# Alimentations.net
KiCad netlist of a schematic drawn in Altium Designer
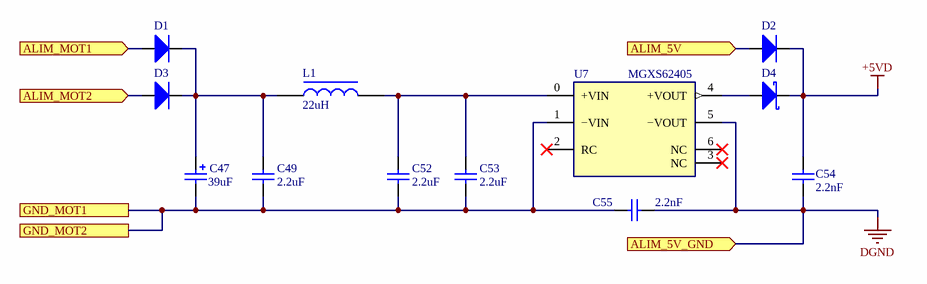
[diagram p0: Alimentations.SchDoc]

(export (version "E")
  (design (tool "Eeschema 10.0.6"))
  (components
    (comp (ref "C47")
      (value "39uF")
      (description "Condensateurs électrolytiques aluminium 100V 39µF Radial, boîtier métallique 7000 heures à 105°C")
      (fields (field (name "Comment") "CAP ALUM RADIAL"))
      (libsource (lib "Driver_Brushless") (part "CAP ALUM 39uF 20% 100V"))
    )
    (comp (ref "C49")
      (value "2.2uF")
      (description "2,2µF ±10% 100V Condensateurs céramique X5R 1206 (3216 métrique)")
      (fields (field (name "Comment") "CAP CER 1203"))
      (libsource (lib "Driver_Brushless") (part "CAP CER 2.2uF 10% 100V 1206"))
    )
    (comp (ref "C52")
      (value "2.2uF")
      (description "2,2µF ±10% 100V Condensateurs céramique X5R 1206 (3216 métrique)")
      (fields (field (name "Comment") "CAP CER 1203"))
      (libsource (lib "Driver_Brushless") (part "CAP CER 2.2uF 10% 100V 1206"))
    )
    (comp (ref "C53")
      (value "2.2uF")
      (description "2,2µF ±10% 100V Condensateurs céramique X5R 1206 (3216 métrique)")
      (fields (field (name "Comment") "CAP CER 1203"))
      (libsource (lib "Driver_Brushless") (part "CAP CER 2.2uF 10% 100V 1206"))
    )
    (comp (ref "C54")
      (value "2.2nF")
      (description "2.2nF ±10% 2000V (2kV) Condensateurs céramique X7R 1812 (4532 métrique)")
      (fields (field (name "Comment") "CAP CER 1812"))
      (libsource (lib "Driver_Brushless") (part "CAP CER 2.2nF 10% 2kV 1812"))
    )
    (comp (ref "C55")
      (value "2.2nF")
      (description "2.2nF ±10% 2000V (2kV) Condensateurs céramique X7R 1812 (4532 métrique)")
      (fields (field (name "Comment") "CAP CER 1812"))
      (libsource (lib "Driver_Brushless") (part "CAP CER 2.2nF 10% 2kV 1812"))
    )
    (comp (ref "D1")
      (value "Diode")
      (footprint "SMC")
      (description "Default Diode")
      (fields (field (name "PUBLISHER") "Altium Limited"))
      (libsource (lib "CommandBoard") (part "Diode"))
    )
    (comp (ref "D2")
      (value "Diode")
      (footprint "SMC")
      (description "Default Diode")
      (fields (field (name "PUBLISHER") "Altium Limited"))
      (libsource (lib "CommandBoard") (part "Diode"))
    )
    (comp (ref "D3")
      (value "Diode")
      (footprint "SMC")
      (description "Default Diode")
      (fields (field (name "PUBLISHER") "Altium Limited"))
      (libsource (lib "CommandBoard") (part "Diode"))
    )
    (comp (ref "D4")
      (value "Diode BAT17")
      (footprint "SOT-23_N")
      (description "Silicon RF Schottky Diode for Mixer Applications in the VHF/UHF Range")
      (fields (field (name "PUBLISHER") "Altium Limited"))
      (libsource (lib "CommandBoard") (part "Diode BAT17"))
    )
    (comp (ref "L1")
      (value "22uH")
      (description "22µH Blindé Bobiné Inducteur 1,05A 259mOhms Non standard")
      (fields (field (name "Comment") "IND SMD 2020"))
      (libsource (lib "Driver_Brushless") (part "IND SMD 22uH 1A 0.26OHM"))
    )
    (comp (ref "U7")
      (value "MGXS62405")
      (description "Module isolé Convertisseurs CC/CC 1 Sortie 5V 1,2A 6V - 60V Entrée")
      (fields (field (name "Comment") "DC DC CONVERTER 6..60V-5V"))
      (libsource (lib "CommandBoard") (part "DC DC CONVERTER 6..60V-5V 6W"))
    )
  )
  (nets
    (net (code "1") (name "+5VD") (class "Default")
      (node (ref "C54") (pin "2") (pinfunction "2_2") (pintype "passive"))
      (node (ref "D2") (pin "2") (pinfunction "K_2") (pintype "passive"))
      (node (ref "D4") (pin "3") (pinfunction "K_3") (pintype "passive"))
    )
    (net (code "2") (name "/ALIM_5V") (class "Default")
      (node (ref "D2") (pin "1") (pinfunction "A_1") (pintype "passive"))
    )
    (net (code "3") (name "/ALIM_MOT1") (class "Default")
      (node (ref "D1") (pin "1") (pinfunction "A_1") (pintype "passive"))
    )
    (net (code "4") (name "/ALIM_MOT2") (class "Default")
      (node (ref "D3") (pin "1") (pinfunction "A_1") (pintype "passive"))
    )
    (net (code "5") (name "/GND_MOT1") (class "Default")
      (node (ref "C47") (pin "2") (pinfunction "2_2") (pintype "passive"))
      (node (ref "C49") (pin "2") (pinfunction "2_2") (pintype "passive"))
      (node (ref "C52") (pin "2") (pinfunction "2_2") (pintype "passive"))
      (node (ref "C53") (pin "2") (pinfunction "2_2") (pintype "passive"))
      (node (ref "C55") (pin "2") (pinfunction "2_2") (pintype "passive"))
      (node (ref "U7") (pin "1") (pinfunction "−VIN_1") (pintype "passive"))
    )
    (net (code "6") (name "DGND") (class "Default")
      (node (ref "C54") (pin "1") (pinfunction "1_1") (pintype "passive"))
      (node (ref "C55") (pin "1") (pinfunction "1_1") (pintype "passive"))
      (node (ref "U7") (pin "5") (pinfunction "−VOUT_5") (pintype "passive"))
    )
    (net (code "7") (name "Net-(D1-K)") (class "Default")
      (node (ref "C47") (pin "1") (pinfunction "1_1") (pintype "passive"))
      (node (ref "C49") (pin "1") (pinfunction "1_1") (pintype "passive"))
      (node (ref "D1") (pin "2") (pinfunction "K_2") (pintype "passive"))
      (node (ref "D3") (pin "2") (pinfunction "K_2") (pintype "passive"))
      (node (ref "L1") (pin "1") (pinfunction "1_1") (pintype "passive"))
    )
    (net (code "8") (name "Net-(D4-A)") (class "Default")
      (node (ref "D4") (pin "1") (pinfunction "A_1") (pintype "passive"))
      (node (ref "U7") (pin "4") (pinfunction "+VOUT_4") (pintype "output"))
    )
    (net (code "9") (name "Net-(U7-+VIN)") (class "Default")
      (node (ref "C52") (pin "1") (pinfunction "1_1") (pintype "passive"))
      (node (ref "C53") (pin "1") (pinfunction "1_1") (pintype "passive"))
      (node (ref "L1") (pin "2") (pinfunction "2_2") (pintype "passive"))
      (node (ref "U7") (pin "0") (pinfunction "+VIN_0") (pintype "power_in"))
    )
    (net (code "10") (name "unconnected-(U7-NC-Pad3)") (class "Default")
      (node (ref "U7") (pin "3") (pinfunction "NC_3") (pintype "power_in+no_connect"))
    )
    (net (code "11") (name "unconnected-(U7-NC-Pad6)") (class "Default")
      (node (ref "U7") (pin "6") (pinfunction "NC_6") (pintype "power_in+no_connect"))
    )
    (net (code "12") (name "unconnected-(U7-RC-Pad2)") (class "Default")
      (node (ref "U7") (pin "2") (pinfunction "RC_2") (pintype "power_in+no_connect"))
    )
  )
)
